# BQ76952_monitor.net
KiCad netlist of a schematic drawn in Altium Designer
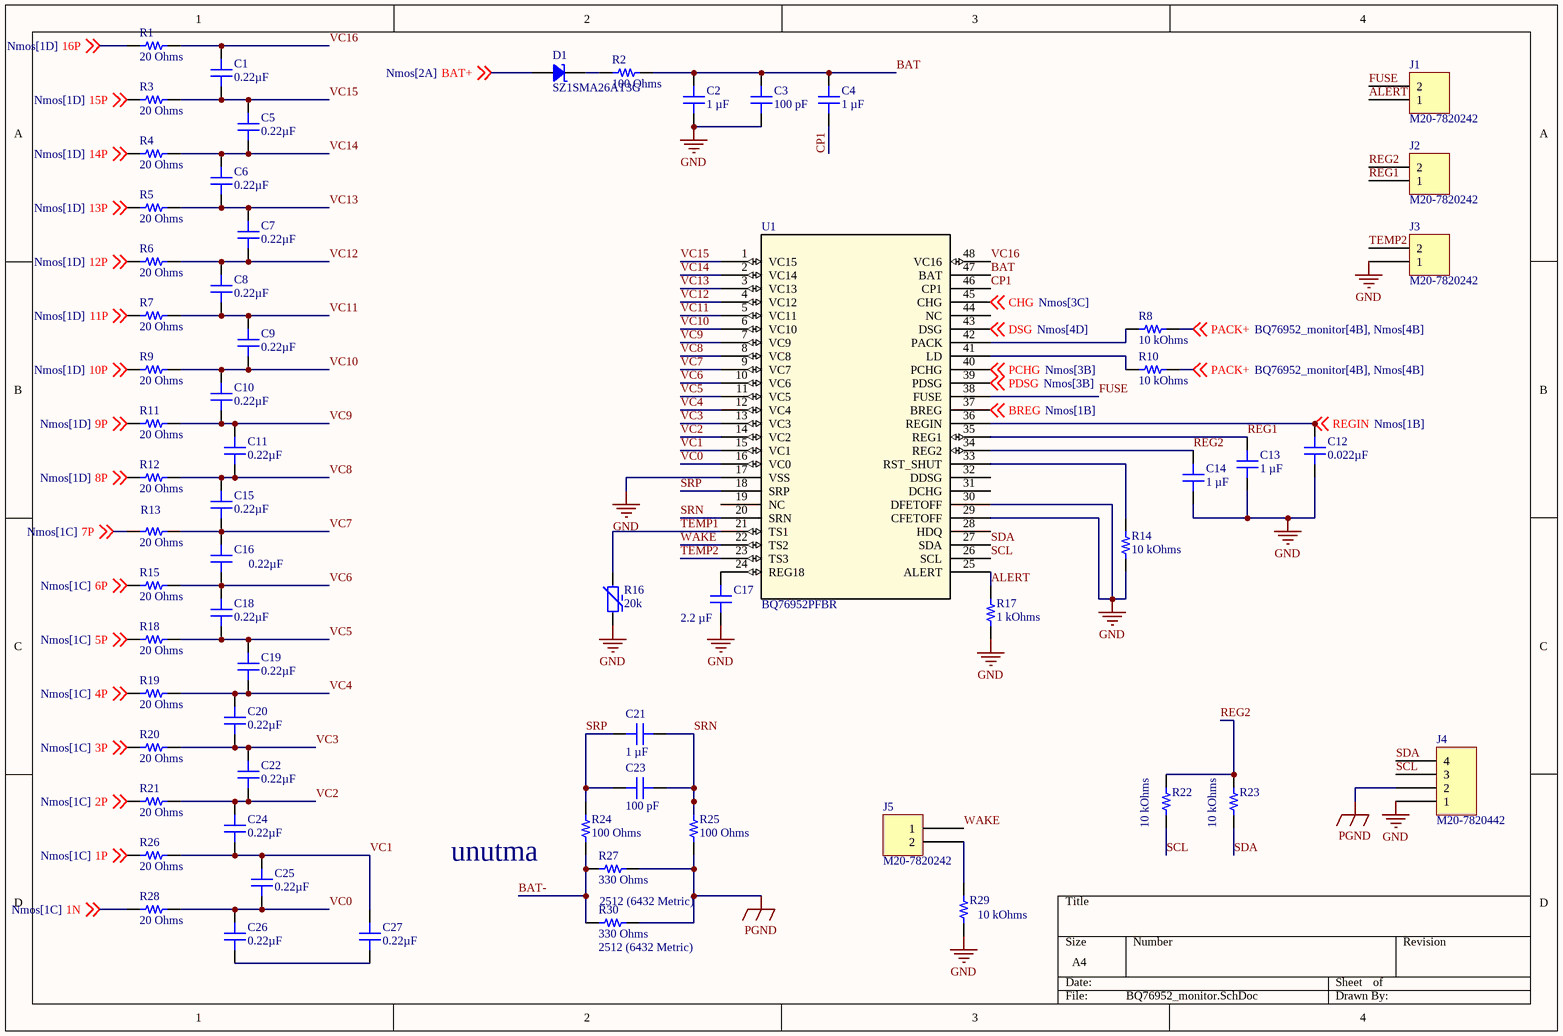
[diagram p0: BQ76952_monitor.SchDoc]

(export (version "E")
  (design (tool "Eeschema 10.0.6"))
  (components
    (comp (ref "C1")
      (value "0.22µF")
      (footprint "CAP 0805_2012")
      (description "CAP CER 0.22UF 16V X7R 0805")
      (fields
        (field (name "PART NUMBER") "0805YC224KAT2A")
        (field (name "CAPACITANCE") "0.22µF")
        (field (name "MANUFACTURER") "AVX Corporation")
      )
      (libsource (lib "Celestial Altium Library - altium_library (1)") (part "Capacitor"))
    )
    (comp (ref "C2")
      (value "1 µF")
      (footprint "CAP 0805_2012")
      (description "CAP MLCC 1UF 10% 100V X7S 0805")
      (fields
        (field (name "PART NUMBER") "HMR212CC7105KG-T")
        (field (name "CAPACITANCE") "1 µF")
        (field (name "MANUFACTURER") "Taiyo Yuden")
      )
      (libsource (lib "Celestial Altium Library - altium_library (1)") (part "Capacitor"))
    )
    (comp (ref "C3")
      (value "100 pF")
      (footprint "CAP 0805_2012")
      (description "CAP CER 100PF 100V C0G/NP0 0805")
      (fields
        (field (name "PART NUMBER") "CL21C101JC61PNC")
        (field (name "CAPACITANCE") "100 pF")
        (field (name "MANUFACTURER") "Samsung Electro-Mechanics")
      )
      (libsource (lib "Celestial Altium Library - altium_library (1)") (part "Capacitor"))
    )
    (comp (ref "C4")
      (value "1 µF")
      (footprint "CAP 0805_2012")
      (description "CAP MLCC 1UF 10% 100V X7S 0805")
      (fields
        (field (name "PART NUMBER") "HMR212CC7105KG-T")
        (field (name "CAPACITANCE") "1 µF")
        (field (name "MANUFACTURER") "Taiyo Yuden")
      )
      (libsource (lib "Celestial Altium Library - altium_library (1)") (part "Capacitor"))
    )
    (comp (ref "C5")
      (value "0.22µF")
      (footprint "CAP 0805_2012")
      (description "CAP CER 0.22UF 16V X7R 0805")
      (fields
        (field (name "PART NUMBER") "0805YC224KAT2A")
        (field (name "CAPACITANCE") "0.22µF")
        (field (name "MANUFACTURER") "AVX Corporation")
      )
      (libsource (lib "Celestial Altium Library - altium_library (1)") (part "Capacitor"))
    )
    (comp (ref "C6")
      (value "0.22µF")
      (footprint "CAP 0805_2012")
      (description "CAP CER 0.22UF 16V X7R 0805")
      (fields
        (field (name "PART NUMBER") "0805YC224KAT2A")
        (field (name "CAPACITANCE") "0.22µF")
        (field (name "MANUFACTURER") "AVX Corporation")
      )
      (libsource (lib "Celestial Altium Library - altium_library (1)") (part "Capacitor"))
    )
    (comp (ref "C7")
      (value "0.22µF")
      (footprint "CAP 0805_2012")
      (description "CAP CER 0.22UF 16V X7R 0805")
      (fields
        (field (name "PART NUMBER") "0805YC224KAT2A")
        (field (name "CAPACITANCE") "0.22µF")
        (field (name "MANUFACTURER") "AVX Corporation")
      )
      (libsource (lib "Celestial Altium Library - altium_library (1)") (part "Capacitor"))
    )
    (comp (ref "C8")
      (value "0.22µF")
      (footprint "CAP 0805_2012")
      (description "CAP CER 0.22UF 16V X7R 0805")
      (fields
        (field (name "PART NUMBER") "0805YC224KAT2A")
        (field (name "CAPACITANCE") "0.22µF")
        (field (name "MANUFACTURER") "AVX Corporation")
      )
      (libsource (lib "Celestial Altium Library - altium_library (1)") (part "Capacitor"))
    )
    (comp (ref "C9")
      (value "0.22µF")
      (footprint "CAP 0805_2012")
      (description "CAP CER 0.22UF 16V X7R 0805")
      (fields
        (field (name "PART NUMBER") "0805YC224KAT2A")
        (field (name "CAPACITANCE") "0.22µF")
        (field (name "MANUFACTURER") "AVX Corporation")
      )
      (libsource (lib "Celestial Altium Library - altium_library (1)") (part "Capacitor"))
    )
    (comp (ref "C10")
      (value "0.22µF")
      (footprint "CAP 0805_2012")
      (description "CAP CER 0.22UF 16V X7R 0805")
      (fields
        (field (name "PART NUMBER") "0805YC224KAT2A")
        (field (name "CAPACITANCE") "0.22µF")
        (field (name "MANUFACTURER") "AVX Corporation")
      )
      (libsource (lib "Celestial Altium Library - altium_library (1)") (part "Capacitor"))
    )
    (comp (ref "C11")
      (value "0.22µF")
      (footprint "CAP 0805_2012")
      (description "CAP CER 0.22UF 16V X7R 0805")
      (fields
        (field (name "PART NUMBER") "0805YC224KAT2A")
        (field (name "CAPACITANCE") "0.22µF")
        (field (name "MANUFACTURER") "AVX Corporation")
      )
      (libsource (lib "Celestial Altium Library - altium_library (1)") (part "Capacitor"))
    )
    (comp (ref "C12")
      (value "0.022µF")
      (footprint "CAP 0805_2012")
      (description "CAP CER 0.022UF 100V X7R 0805")
      (fields
        (field (name "PART NUMBER") "08051C223K4T2A")
        (field (name "CAPACITANCE") "0.022µF")
        (field (name "MANUFACTURER") "AVX Corporation")
      )
      (libsource (lib "Celestial Altium Library - altium_library (1)") (part "Capacitor"))
    )
    (comp (ref "C13")
      (value "1 µF")
      (footprint "CAP 0805_2012")
      (description "CAP CER 1UF 16V Y5V 0805")
      (fields
        (field (name "PART NUMBER") "C0805C105M4VAC7800")
        (field (name "CAPACITANCE") "1 µF")
        (field (name "MANUFACTURER") "KEMET")
      )
      (libsource (lib "Celestial Altium Library - altium_library (1)") (part "Capacitor"))
    )
    (comp (ref "C14")
      (value "1 µF")
      (footprint "CAP 0805_2012")
      (description "CAP CER 1UF 16V Y5V 0805")
      (fields
        (field (name "PART NUMBER") "C0805C105M4VAC7800")
        (field (name "CAPACITANCE") "1 µF")
        (field (name "MANUFACTURER") "KEMET")
      )
      (libsource (lib "Celestial Altium Library - altium_library (1)") (part "Capacitor"))
    )
    (comp (ref "C15")
      (value "0.22µF")
      (footprint "CAP 0805_2012")
      (description "CAP CER 0.22UF 16V X7R 0805")
      (fields
        (field (name "PART NUMBER") "0805YC224KAT2A")
        (field (name "CAPACITANCE") "0.22µF")
        (field (name "MANUFACTURER") "AVX Corporation")
      )
      (libsource (lib "Celestial Altium Library - altium_library (1)") (part "Capacitor"))
    )
    (comp (ref "C16")
      (value "0.22µF")
      (footprint "CAP 0805_2012")
      (description "CAP CER 0.22UF 16V X7R 0805")
      (fields
        (field (name "PART NUMBER") "0805YC224KAT2A")
        (field (name "CAPACITANCE") "0.22µF")
        (field (name "MANUFACTURER") "AVX Corporation")
      )
      (libsource (lib "Celestial Altium Library - altium_library (1)") (part "Capacitor"))
    )
    (comp (ref "C17")
      (value "GRM31MR71E225KA93L")
      (footprint "MURATA CAP GRM31M 1206_3216")
      (description "CAP CER 2.2UF 25V X7R 1206")
      (fields
        (field (name "CAPACITANCE") "2.2 µF")
        (field (name "MANUFACTURER") "Murata Electronics")
        (field (name "TOLERANCE") "±10%")
      )
      (libsource (lib "Celestial Altium Library - altium_library (1)") (part "Capacitor"))
    )
    (comp (ref "C18")
      (value "0.22µF")
      (footprint "CAP 0805_2012")
      (description "CAP CER 0.22UF 16V X7R 0805")
      (fields
        (field (name "PART NUMBER") "0805YC224KAT2A")
        (field (name "CAPACITANCE") "0.22µF")
        (field (name "MANUFACTURER") "AVX Corporation")
      )
      (libsource (lib "Celestial Altium Library - altium_library (1)") (part "Capacitor"))
    )
    (comp (ref "C19")
      (value "0.22µF")
      (footprint "CAP 0805_2012")
      (description "CAP CER 0.22UF 16V X7R 0805")
      (fields
        (field (name "PART NUMBER") "0805YC224KAT2A")
        (field (name "CAPACITANCE") "0.22µF")
        (field (name "MANUFACTURER") "AVX Corporation")
      )
      (libsource (lib "Celestial Altium Library - altium_library (1)") (part "Capacitor"))
    )
    (comp (ref "C20")
      (value "0.22µF")
      (footprint "CAP 0805_2012")
      (description "CAP CER 0.22UF 16V X7R 0805")
      (fields
        (field (name "PART NUMBER") "0805YC224KAT2A")
        (field (name "CAPACITANCE") "0.22µF")
        (field (name "MANUFACTURER") "AVX Corporation")
      )
      (libsource (lib "Celestial Altium Library - altium_library (1)") (part "Capacitor"))
    )
    (comp (ref "C21")
      (value "1 µF")
      (footprint "CAP 0805_2012")
      (description "CAP MLCC 1UF 10% 100V X7S 0805")
      (fields
        (field (name "PART NUMBER") "HMR212CC7105KG-T")
        (field (name "CAPACITANCE") "1 µF")
        (field (name "MANUFACTURER") "Taiyo Yuden")
      )
      (libsource (lib "Celestial Altium Library - altium_library (1)") (part "Capacitor"))
    )
    (comp (ref "C22")
      (value "0.22µF")
      (footprint "CAP 0805_2012")
      (description "CAP CER 0.22UF 16V X7R 0805")
      (fields
        (field (name "PART NUMBER") "0805YC224KAT2A")
        (field (name "CAPACITANCE") "0.22µF")
        (field (name "MANUFACTURER") "AVX Corporation")
      )
      (libsource (lib "Celestial Altium Library - altium_library (1)") (part "Capacitor"))
    )
    (comp (ref "C23")
      (value "100 pF")
      (footprint "CAP 0805_2012")
      (description "CAP CER 100PF 100V C0G/NP0 0805")
      (fields
        (field (name "PART NUMBER") "CL21C101JC61PNC")
        (field (name "CAPACITANCE") "100 pF")
        (field (name "MANUFACTURER") "Samsung Electro-Mechanics")
      )
      (libsource (lib "Celestial Altium Library - altium_library (1)") (part "Capacitor"))
    )
    (comp (ref "C24")
      (value "0.22µF")
      (footprint "CAP 0805_2012")
      (description "CAP CER 0.22UF 16V X7R 0805")
      (fields
        (field (name "PART NUMBER") "0805YC224KAT2A")
        (field (name "CAPACITANCE") "0.22µF")
        (field (name "MANUFACTURER") "AVX Corporation")
      )
      (libsource (lib "Celestial Altium Library - altium_library (1)") (part "Capacitor"))
    )
    (comp (ref "C25")
      (value "0.22µF")
      (footprint "CAP 0805_2012")
      (description "CAP CER 0.22UF 16V X7R 0805")
      (fields
        (field (name "PART NUMBER") "0805YC224KAT2A")
        (field (name "CAPACITANCE") "0.22µF")
        (field (name "MANUFACTURER") "AVX Corporation")
      )
      (libsource (lib "Celestial Altium Library - altium_library (1)") (part "Capacitor"))
    )
    (comp (ref "C26")
      (value "0.22µF")
      (footprint "CAP 0805_2012")
      (description "CAP CER 0.22UF 16V X7R 0805")
      (fields
        (field (name "PART NUMBER") "0805YC224KAT2A")
        (field (name "CAPACITANCE") "0.22µF")
        (field (name "MANUFACTURER") "AVX Corporation")
      )
      (libsource (lib "Celestial Altium Library - altium_library (1)") (part "Capacitor"))
    )
    (comp (ref "C27")
      (value "0.22µF")
      (footprint "CAP 0805_2012")
      (description "CAP CER 0.22UF 16V X7R 0805")
      (fields
        (field (name "PART NUMBER") "0805YC224KAT2A")
        (field (name "CAPACITANCE") "0.22µF")
        (field (name "MANUFACTURER") "AVX Corporation")
      )
      (libsource (lib "Celestial Altium Library - altium_library (1)") (part "Capacitor"))
    )
    (comp (ref "D1")
      (value "SZ1SMA26AT3G")
      (footprint "DO214AC SMA")
      (description "TVS DIODE 26VWM 42.1VC SMA")
      (fields (field (name "MANUFACTURER") "Littelfuse Inc."))
      (libsource (lib "Celestial Altium Library - altium_library (1)") (part "DIODE TVS UNI"))
    )
    (comp (ref "J1")
      (value "M20-7820242")
      (footprint "HARWIN M20-7820245")
      (description "CONN RCPT 2POS 0.1 GOLD PCB")
      (fields (field (name "MANUFACTURER") "Harwin Inc."))
      (libsource (lib "Celestial Altium Library - altium_library (1)") (part "2 Pin"))
    )
    (comp (ref "J2")
      (value "M20-7820242")
      (footprint "HARWIN M20-7820245")
      (description "CONN RCPT 2POS 0.1 GOLD PCB")
      (fields (field (name "MANUFACTURER") "Harwin Inc."))
      (libsource (lib "Celestial Altium Library - altium_library (1)") (part "2 Pin"))
    )
    (comp (ref "J3")
      (value "M20-7820242")
      (footprint "HARWIN M20-7820245")
      (description "CONN RCPT 2POS 0.1 GOLD PCB")
      (fields (field (name "MANUFACTURER") "Harwin Inc."))
      (libsource (lib "Celestial Altium Library - altium_library (1)") (part "2 Pin"))
    )
    (comp (ref "J4")
      (value "M20-7820442")
      (footprint "HARWIN M20-7820445")
      (description "CONN RCPT 4POS 0.1 GOLD PCB")
      (fields (field (name "MANUFACTURER") "Harwin Inc."))
      (libsource (lib "Celestial Altium Library - altium_library (1)") (part "4 Pin"))
    )
    (comp (ref "J5")
      (value "M20-7820242")
      (footprint "HARWIN M20-7820245")
      (description "CONN RCPT 2POS 0.1 GOLD PCB")
      (fields (field (name "MANUFACTURER") "Harwin Inc."))
      (libsource (lib "") (part "2 Pin_1"))
    )
    (comp (ref "R1")
      (value "20 Ohms")
      (footprint "RES 1206_3216")
      (description "RES SMD 20 OHM 1% 1/2W 1206")
      (fields (field (name "PART NUMBER") "ESR18EZPF20R0") (field (name "MANUFACTURER") "Rohm Semiconductor"))
      (libsource (lib "Celestial Altium Library - altium_library (1)") (part "Resistor"))
    )
    (comp (ref "R2")
      (value "100 Ohms")
      (footprint "RES 1206_3216")
      (description "RES 100 OHM 0.1% 1/8W 1206")
      (fields
        (field (name "PART NUMBER") "RNCS1206BKE100R")
        (field (name "MANUFACTURER") "Stackpole Electronics Inc")
      )
      (libsource (lib "Celestial Altium Library - altium_library (1)") (part "Resistor"))
    )
    (comp (ref "R3")
      (value "20 Ohms")
      (footprint "RES 1206_3216")
      (description "RES SMD 20 OHM 1% 1/2W 1206")
      (fields (field (name "PART NUMBER") "ESR18EZPF20R0") (field (name "MANUFACTURER") "Rohm Semiconductor"))
      (libsource (lib "Celestial Altium Library - altium_library (1)") (part "Resistor"))
    )
    (comp (ref "R4")
      (value "20 Ohms")
      (footprint "RES 1206_3216")
      (description "RES SMD 20 OHM 1% 1/2W 1206")
      (fields (field (name "PART NUMBER") "ESR18EZPF20R0") (field (name "MANUFACTURER") "Rohm Semiconductor"))
      (libsource (lib "Celestial Altium Library - altium_library (1)") (part "Resistor"))
    )
    (comp (ref "R5")
      (value "20 Ohms")
      (footprint "RES 1206_3216")
      (description "RES SMD 20 OHM 1% 1/2W 1206")
      (fields (field (name "PART NUMBER") "ESR18EZPF20R0") (field (name "MANUFACTURER") "Rohm Semiconductor"))
      (libsource (lib "Celestial Altium Library - altium_library (1)") (part "Resistor"))
    )
    (comp (ref "R6")
      (value "20 Ohms")
      (footprint "RES 1206_3216")
      (description "RES SMD 20 OHM 1% 1/2W 1206")
      (fields (field (name "PART NUMBER") "ESR18EZPF20R0") (field (name "MANUFACTURER") "Rohm Semiconductor"))
      (libsource (lib "Celestial Altium Library - altium_library (1)") (part "Resistor"))
    )
    (comp (ref "R7")
      (value "20 Ohms")
      (footprint "RES 1206_3216")
      (description "RES SMD 20 OHM 1% 1/2W 1206")
      (fields (field (name "PART NUMBER") "ESR18EZPF20R0") (field (name "MANUFACTURER") "Rohm Semiconductor"))
      (libsource (lib "Celestial Altium Library - altium_library (1)") (part "Resistor"))
    )
    (comp (ref "R8")
      (value "10 kOhms")
      (footprint "RES 1206_3216")
      (description "RES SMD 10K OHM 0.1% 1/4W 1206")
      (fields
        (field (name "PART NUMBER") "ERA-8ARB103V")
        (field (name "MANUFACTURER") "Panasonic Electronic Components")
      )
      (libsource (lib "Celestial Altium Library - altium_library (1)") (part "Resistor"))
    )
    (comp (ref "R9")
      (value "20 Ohms")
      (footprint "RES 1206_3216")
      (description "RES SMD 20 OHM 1% 1/2W 1206")
      (fields (field (name "PART NUMBER") "ESR18EZPF20R0") (field (name "MANUFACTURER") "Rohm Semiconductor"))
      (libsource (lib "Celestial Altium Library - altium_library (1)") (part "Resistor"))
    )
    (comp (ref "R10")
      (value "10 kOhms")
      (footprint "RES 1206_3216")
      (description "RES SMD 10K OHM 0.1% 1/4W 1206")
      (fields
        (field (name "PART NUMBER") "ERA-8ARB103V")
        (field (name "MANUFACTURER") "Panasonic Electronic Components")
      )
      (libsource (lib "Celestial Altium Library - altium_library (1)") (part "Resistor"))
    )
    (comp (ref "R11")
      (value "20 Ohms")
      (footprint "RES 1206_3216")
      (description "RES SMD 20 OHM 1% 1/2W 1206")
      (fields (field (name "PART NUMBER") "ESR18EZPF20R0") (field (name "MANUFACTURER") "Rohm Semiconductor"))
      (libsource (lib "Celestial Altium Library - altium_library (1)") (part "Resistor"))
    )
    (comp (ref "R12")
      (value "20 Ohms")
      (footprint "RES 1206_3216")
      (description "RES SMD 20 OHM 1% 1/2W 1206")
      (fields (field (name "PART NUMBER") "ESR18EZPF20R0") (field (name "MANUFACTURER") "Rohm Semiconductor"))
      (libsource (lib "Celestial Altium Library - altium_library (1)") (part "Resistor"))
    )
    (comp (ref "R13")
      (value "20 Ohms")
      (footprint "RES 1206_3216")
      (description "RES SMD 20 OHM 1% 1/2W 1206")
      (fields (field (name "PART NUMBER") "ESR18EZPF20R0") (field (name "MANUFACTURER") "Rohm Semiconductor"))
      (libsource (lib "Celestial Altium Library - altium_library (1)") (part "Resistor"))
    )
    (comp (ref "R14")
      (value "10 kOhms")
      (footprint "RES 1206_3216")
      (description "RES SMD 10K OHM 0.1% 1/4W 1206")
      (fields
        (field (name "PART NUMBER") "ERA-8ARB103V")
        (field (name "MANUFACTURER") "Panasonic Electronic Components")
      )
      (libsource (lib "Celestial Altium Library - altium_library (1)") (part "Resistor"))
    )
    (comp (ref "R15")
      (value "20 Ohms")
      (footprint "RES 1206_3216")
      (description "RES SMD 20 OHM 1% 1/2W 1206")
      (fields (field (name "PART NUMBER") "ESR18EZPF20R0") (field (name "MANUFACTURER") "Rohm Semiconductor"))
      (libsource (lib "Celestial Altium Library - altium_library (1)") (part "Resistor"))
    )
    (comp (ref "R16")
      (value "20k")
      (footprint "NTC 0805_2012")
      (description "THERMISTOR NTC 20KOHM 4000K 0805")
      (fields
        (field (name "PART NUMBER") "NHQM203B400T5")
        (field (name "MANUFACTURER") "Amphenol Advanced Sensors")
      )
      (libsource (lib "Celestial Altium Library - altium_library (1)") (part "Thermistor"))
    )
    (comp (ref "R17")
      (value "1 kOhms")
      (footprint "RES 1206_3216")
      (description "RES SMD 1K OHM 5% 1/4W 1206")
      (fields
        (field (name "PART NUMBER") "ERJ-8GEYJ102V")
        (field (name "MANUFACTURER") "Panasonic Electronic Components")
      )
      (libsource (lib "Celestial Altium Library - altium_library (1)") (part "Resistor"))
    )
    (comp (ref "R18")
      (value "20 Ohms")
      (footprint "RES 1206_3216")
      (description "RES SMD 20 OHM 1% 1/2W 1206")
      (fields (field (name "PART NUMBER") "ESR18EZPF20R0") (field (name "MANUFACTURER") "Rohm Semiconductor"))
      (libsource (lib "Celestial Altium Library - altium_library (1)") (part "Resistor"))
    )
    (comp (ref "R19")
      (value "20 Ohms")
      (footprint "RES 1206_3216")
      (description "RES SMD 20 OHM 1% 1/2W 1206")
      (fields (field (name "PART NUMBER") "ESR18EZPF20R0") (field (name "MANUFACTURER") "Rohm Semiconductor"))
      (libsource (lib "Celestial Altium Library - altium_library (1)") (part "Resistor"))
    )
    (comp (ref "R20")
      (value "20 Ohms")
      (footprint "RES 1206_3216")
      (description "RES SMD 20 OHM 1% 1/2W 1206")
      (fields (field (name "PART NUMBER") "ESR18EZPF20R0") (field (name "MANUFACTURER") "Rohm Semiconductor"))
      (libsource (lib "Celestial Altium Library - altium_library (1)") (part "Resistor"))
    )
    (comp (ref "R21")
      (value "20 Ohms")
      (footprint "RES 1206_3216")
      (description "RES SMD 20 OHM 1% 1/2W 1206")
      (fields (field (name "PART NUMBER") "ESR18EZPF20R0") (field (name "MANUFACTURER") "Rohm Semiconductor"))
      (libsource (lib "Celestial Altium Library - altium_library (1)") (part "Resistor"))
    )
    (comp (ref "R22")
      (value "10 kOhms")
      (footprint "RES 1206_3216")
      (description "RES SMD 10K OHM 0.1% 1/4W 1206")
      (fields
        (field (name "PART NUMBER") "ERA-8ARB103V")
        (field (name "MANUFACTURER") "Panasonic Electronic Components")
      )
      (libsource (lib "Celestial Altium Library - altium_library (1)") (part "Resistor"))
    )
    (comp (ref "R23")
      (value "10 kOhms")
      (footprint "RES 1206_3216")
      (description "RES SMD 10K OHM 0.1% 1/4W 1206")
      (fields
        (field (name "PART NUMBER") "ERA-8ARB103V")
        (field (name "MANUFACTURER") "Panasonic Electronic Components")
      )
      (libsource (lib "Celestial Altium Library - altium_library (1)") (part "Resistor"))
    )
    (comp (ref "R24")
      (value "100 Ohms")
      (footprint "RES 1206_3216")
      (description "RES 100 OHM 0.1% 1/8W 1206")
      (fields
        (field (name "PART NUMBER") "RNCS1206BKE100R")
        (field (name "MANUFACTURER") "Stackpole Electronics Inc")
      )
      (libsource (lib "Celestial Altium Library - altium_library (1)") (part "Resistor"))
    )
    (comp (ref "R25")
      (value "100 Ohms")
      (footprint "RES 1206_3216")
      (description "RES 100 OHM 0.1% 1/8W 1206")
      (fields
        (field (name "PART NUMBER") "RNCS1206BKE100R")
        (field (name "MANUFACTURER") "Stackpole Electronics Inc")
      )
      (libsource (lib "Celestial Altium Library - altium_library (1)") (part "Resistor"))
    )
    (comp (ref "R26")
      (value "20 Ohms")
      (footprint "RES 1206_3216")
      (description "RES SMD 20 OHM 1% 1/2W 1206")
      (fields (field (name "PART NUMBER") "ESR18EZPF20R0") (field (name "MANUFACTURER") "Rohm Semiconductor"))
      (libsource (lib "Celestial Altium Library - altium_library (1)") (part "Resistor"))
    )
    (comp (ref "R27")
      (value "330 Ohms")
      (footprint "STACKPOLE CSR2512")
      (description "RES SMD 330 OHM 1% 2W 2512")
      (fields
        (field (name "PART NUMBER") "CRM2512-FX-3300ELF")
        (field (name "PACKAGE / CASE") "2512 (6432 Metric)")
        (field (name "MANUFACTURER") "Bourns Inc.")
      )
      (libsource (lib "Celestial Altium Library - altium_library (1)") (part "Resistor"))
    )
    (comp (ref "R28")
      (value "20 Ohms")
      (footprint "RES 1206_3216")
      (description "RES SMD 20 OHM 1% 1/2W 1206")
      (fields (field (name "PART NUMBER") "ESR18EZPF20R0") (field (name "MANUFACTURER") "Rohm Semiconductor"))
      (libsource (lib "Celestial Altium Library - altium_library (1)") (part "Resistor"))
    )
    (comp (ref "R29")
      (value "10 kOhms")
      (footprint "RES 1206_3216")
      (description "RES SMD 10K OHM 0.1% 1/4W 1206")
      (fields
        (field (name "PART NUMBER") "ERA-8ARB103V")
        (field (name "MANUFACTURER") "Panasonic Electronic Components")
      )
      (libsource (lib "Celestial Altium Library - altium_library (1)") (part "Resistor"))
    )
    (comp (ref "R30")
      (value "330 Ohms")
      (footprint "STACKPOLE CSR2512")
      (description "RES SMD 330 OHM 1% 2W 2512")
      (fields
        (field (name "PART NUMBER") "CRM2512-FX-3300ELF")
        (field (name "PACKAGE / CASE") "2512 (6432 Metric)")
        (field (name "MANUFACTURER") "Bourns Inc.")
      )
      (libsource (lib "Celestial Altium Library - altium_library (1)") (part "Resistor"))
    )
    (comp (ref "U1")
      (value "BQ76952PFBR")
      (footprint "QFP_2PFBR_TEX")
      (description "No Description Available")
      (libsource (lib "BQ76952PFBR") (part "BQ76952PFBR"))
    )
  )
  (nets
    (net (code "1") (name "/ALERT") (class "Default")
      (node (ref "J1") (pin "1") (pinfunction "1_1") (pintype "passive"))
      (node (ref "R17") (pin "2") (pinfunction "2_2") (pintype "passive"))
      (node (ref "U1") (pin "25") (pinfunction "ALERT_25") (pintype "passive"))
    )
    (net (code "2") (name "/BAT") (class "Default")
      (node (ref "C2") (pin "2") (pinfunction "2_2") (pintype "passive"))
      (node (ref "C3") (pin "2") (pinfunction "2_2") (pintype "passive"))
      (node (ref "C4") (pin "2") (pinfunction "2_2") (pintype "passive"))
      (node (ref "R2") (pin "2") (pinfunction "2_2") (pintype "passive"))
      (node (ref "U1") (pin "47") (pinfunction "BAT_47") (pintype "passive"))
    )
    (net (code "3") (name "/BAT-") (class "Default")
      (node (ref "R24") (pin "1") (pinfunction "1_1") (pintype "passive"))
      (node (ref "R27") (pin "2") (pinfunction "2_2") (pintype "passive"))
      (node (ref "R30") (pin "2") (pinfunction "2_2") (pintype "passive"))
    )
    (net (code "4") (name "/CP1") (class "Default")
      (node (ref "C4") (pin "1") (pinfunction "1_1") (pintype "passive"))
      (node (ref "U1") (pin "46") (pinfunction "CP1_46") (pintype "passive"))
    )
    (net (code "5") (name "/FUSE") (class "Default")
      (node (ref "J1") (pin "2") (pinfunction "2_2") (pintype "passive"))
      (node (ref "U1") (pin "38") (pinfunction "FUSE_38") (pintype "passive"))
    )
    (net (code "6") (name "/REG1") (class "Default")
      (node (ref "C13") (pin "2") (pinfunction "2_2") (pintype "passive"))
      (node (ref "J2") (pin "1") (pinfunction "1_1") (pintype "passive"))
      (node (ref "U1") (pin "35") (pinfunction "REG1_35") (pintype "bidirectional"))
    )
    (net (code "7") (name "/REG2") (class "Default")
      (node (ref "C14") (pin "2") (pinfunction "2_2") (pintype "passive"))
      (node (ref "J2") (pin "2") (pinfunction "2_2") (pintype "passive"))
      (node (ref "R22") (pin "2") (pinfunction "2_2") (pintype "passive"))
      (node (ref "R23") (pin "2") (pinfunction "2_2") (pintype "passive"))
      (node (ref "U1") (pin "34") (pinfunction "REG2_34") (pintype "bidirectional"))
    )
    (net (code "8") (name "/SCL") (class "Default")
      (node (ref "J4") (pin "3") (pinfunction "3_3") (pintype "passive"))
      (node (ref "R22") (pin "1") (pinfunction "1_1") (pintype "passive"))
      (node (ref "U1") (pin "26") (pinfunction "SCL_26") (pintype "passive"))
    )
    (net (code "9") (name "/SDA") (class "Default")
      (node (ref "J4") (pin "4") (pinfunction "4_4") (pintype "passive"))
      (node (ref "R23") (pin "1") (pinfunction "1_1") (pintype "passive"))
      (node (ref "U1") (pin "27") (pinfunction "SDA_27") (pintype "passive"))
    )
    (net (code "10") (name "/SRN") (class "Default")
      (node (ref "C21") (pin "1") (pinfunction "1_1") (pintype "passive"))
      (node (ref "C23") (pin "1") (pinfunction "1_1") (pintype "passive"))
      (node (ref "R25") (pin "2") (pinfunction "2_2") (pintype "passive"))
      (node (ref "U1") (pin "20") (pinfunction "SRN_20") (pintype "passive"))
    )
    (net (code "11") (name "/SRP") (class "Default")
      (node (ref "C21") (pin "2") (pinfunction "2_2") (pintype "passive"))
      (node (ref "C23") (pin "2") (pinfunction "2_2") (pintype "passive"))
      (node (ref "R24") (pin "2") (pinfunction "2_2") (pintype "passive"))
      (node (ref "U1") (pin "18") (pinfunction "SRP_18") (pintype "passive"))
    )
    (net (code "12") (name "/TEMP1") (class "Default")
      (node (ref "R16") (pin "2") (pinfunction "2_2") (pintype "passive"))
      (node (ref "U1") (pin "21") (pinfunction "TS1_21") (pintype "bidirectional"))
    )
    (net (code "13") (name "/TEMP2") (class "Default")
      (node (ref "J3") (pin "2") (pinfunction "2_2") (pintype "passive"))
      (node (ref "U1") (pin "23") (pinfunction "TS3_23") (pintype "bidirectional"))
    )
    (net (code "14") (name "/VC0") (class "Default")
      (node (ref "C25") (pin "1") (pinfunction "1_1") (pintype "passive"))
      (node (ref "C26") (pin "2") (pinfunction "2_2") (pintype "passive"))
      (node (ref "R28") (pin "2") (pinfunction "2_2") (pintype "passive"))
      (node (ref "U1") (pin "16") (pinfunction "VC0_16") (pintype "bidirectional"))
    )
    (net (code "15") (name "/VC1") (class "Default")
      (node (ref "C24") (pin "1") (pinfunction "1_1") (pintype "passive"))
      (node (ref "C25") (pin "2") (pinfunction "2_2") (pintype "passive"))
      (node (ref "C27") (pin "2") (pinfunction "2_2") (pintype "passive"))
      (node (ref "R26") (pin "2") (pinfunction "2_2") (pintype "passive"))
      (node (ref "U1") (pin "15") (pinfunction "VC1_15") (pintype "bidirectional"))
    )
    (net (code "16") (name "/VC2") (class "Default")
      (node (ref "C22") (pin "1") (pinfunction "1_1") (pintype "passive"))
      (node (ref "C24") (pin "2") (pinfunction "2_2") (pintype "passive"))
      (node (ref "R21") (pin "2") (pinfunction "2_2") (pintype "passive"))
      (node (ref "U1") (pin "14") (pinfunction "VC2_14") (pintype "bidirectional"))
    )
    (net (code "17") (name "/VC3") (class "Default")
      (node (ref "C20") (pin "1") (pinfunction "1_1") (pintype "passive"))
      (node (ref "C22") (pin "2") (pinfunction "2_2") (pintype "passive"))
      (node (ref "R20") (pin "2") (pinfunction "2_2") (pintype "passive"))
      (node (ref "U1") (pin "13") (pinfunction "VC3_13") (pintype "bidirectional"))
    )
    (net (code "18") (name "/VC4") (class "Default")
      (node (ref "C19") (pin "1") (pinfunction "1_1") (pintype "passive"))
      (node (ref "C20") (pin "2") (pinfunction "2_2") (pintype "passive"))
      (node (ref "R19") (pin "2") (pinfunction "2_2") (pintype "passive"))
      (node (ref "U1") (pin "12") (pinfunction "VC4_12") (pintype "bidirectional"))
    )
    (net (code "19") (name "/VC5") (class "Default")
      (node (ref "C18") (pin "1") (pinfunction "1_1") (pintype "passive"))
      (node (ref "C19") (pin "2") (pinfunction "2_2") (pintype "passive"))
      (node (ref "R18") (pin "2") (pinfunction "2_2") (pintype "passive"))
      (node (ref "U1") (pin "11") (pinfunction "VC5_11") (pintype "bidirectional"))
    )
    (net (code "20") (name "/VC6") (class "Default")
      (node (ref "C16") (pin "1") (pinfunction "1_1") (pintype "passive"))
      (node (ref "C18") (pin "2") (pinfunction "2_2") (pintype "passive"))
      (node (ref "R15") (pin "2") (pinfunction "2_2") (pintype "passive"))
      (node (ref "U1") (pin "10") (pinfunction "VC6_10") (pintype "bidirectional"))
    )
    (net (code "21") (name "/VC7") (class "Default")
      (node (ref "C15") (pin "1") (pinfunction "1_1") (pintype "passive"))
      (node (ref "C16") (pin "2") (pinfunction "2_2") (pintype "passive"))
      (node (ref "R13") (pin "2") (pinfunction "2_2") (pintype "passive"))
      (node (ref "U1") (pin "9") (pinfunction "VC7_9") (pintype "bidirectional"))
    )
    (net (code "22") (name "/VC8") (class "Default")
      (node (ref "C11") (pin "1") (pinfunction "1_1") (pintype "passive"))
      (node (ref "C15") (pin "2") (pinfunction "2_2") (pintype "passive"))
      (node (ref "R12") (pin "2") (pinfunction "2_2") (pintype "passive"))
      (node (ref "U1") (pin "8") (pinfunction "VC8_8") (pintype "bidirectional"))
    )
    (net (code "23") (name "/VC9") (class "Default")
      (node (ref "C10") (pin "1") (pinfunction "1_1") (pintype "passive"))
      (node (ref "C11") (pin "2") (pinfunction "2_2") (pintype "passive"))
      (node (ref "R11") (pin "2") (pinfunction "2_2") (pintype "passive"))
      (node (ref "U1") (pin "7") (pinfunction "VC9_7") (pintype "bidirectional"))
    )
    (net (code "24") (name "/VC10") (class "Default")
      (node (ref "C10") (pin "2") (pinfunction "2_2") (pintype "passive"))
      (node (ref "C9") (pin "1") (pinfunction "1_1") (pintype "passive"))
      (node (ref "R9") (pin "2") (pinfunction "2_2") (pintype "passive"))
      (node (ref "U1") (pin "6") (pinfunction "VC10_6") (pintype "bidirectional"))
    )
    (net (code "25") (name "/VC11") (class "Default")
      (node (ref "C8") (pin "1") (pinfunction "1_1") (pintype "passive"))
      (node (ref "C9") (pin "2") (pinfunction "2_2") (pintype "passive"))
      (node (ref "R7") (pin "2") (pinfunction "2_2") (pintype "passive"))
      (node (ref "U1") (pin "5") (pinfunction "VC11_5") (pintype "bidirectional"))
    )
    (net (code "26") (name "/VC12") (class "Default")
      (node (ref "C7") (pin "1") (pinfunction "1_1") (pintype "passive"))
      (node (ref "C8") (pin "2") (pinfunction "2_2") (pintype "passive"))
      (node (ref "R6") (pin "2") (pinfunction "2_2") (pintype "passive"))
      (node (ref "U1") (pin "4") (pinfunction "VC12_4") (pintype "bidirectional"))
    )
    (net (code "27") (name "/VC13") (class "Default")
      (node (ref "C6") (pin "1") (pinfunction "1_1") (pintype "passive"))
      (node (ref "C7") (pin "2") (pinfunction "2_2") (pintype "passive"))
      (node (ref "R5") (pin "2") (pinfunction "2_2") (pintype "passive"))
      (node (ref "U1") (pin "3") (pinfunction "VC13_3") (pintype "bidirectional"))
    )
    (net (code "28") (name "/VC14") (class "Default")
      (node (ref "C5") (pin "1") (pinfunction "1_1") (pintype "passive"))
      (node (ref "C6") (pin "2") (pinfunction "2_2") (pintype "passive"))
      (node (ref "R4") (pin "2") (pinfunction "2_2") (pintype "passive"))
      (node (ref "U1") (pin "2") (pinfunction "VC14_2") (pintype "bidirectional"))
    )
    (net (code "29") (name "/VC15") (class "Default")
      (node (ref "C1") (pin "1") (pinfunction "1_1") (pintype "passive"))
      (node (ref "C5") (pin "2") (pinfunction "2_2") (pintype "passive"))
      (node (ref "R3") (pin "2") (pinfunction "2_2") (pintype "passive"))
      (node (ref "U1") (pin "1") (pinfunction "VC15_1") (pintype "bidirectional"))
    )
    (net (code "30") (name "/VC16") (class "Default")
      (node (ref "C1") (pin "2") (pinfunction "2_2") (pintype "passive"))
      (node (ref "R1") (pin "2") (pinfunction "2_2") (pintype "passive"))
      (node (ref "U1") (pin "48") (pinfunction "VC16_48") (pintype "bidirectional"))
    )
    (net (code "31") (name "/WAKE") (class "Default")
      (node (ref "J5") (pin "1") (pinfunction "1_1") (pintype "passive"))
      (node (ref "U1") (pin "22") (pinfunction "TS2_22") (pintype "bidirectional"))
    )
    (net (code "32") (name "1N") (class "Default")
      (node (ref "R28") (pin "1") (pinfunction "1_1") (pintype "passive"))
    )
    (net (code "33") (name "1P") (class "Default")
      (node (ref "R26") (pin "1") (pinfunction "1_1") (pintype "passive"))
    )
    (net (code "34") (name "2P") (class "Default")
      (node (ref "R21") (pin "1") (pinfunction "1_1") (pintype "passive"))
    )
    (net (code "35") (name "3P") (class "Default")
      (node (ref "R20") (pin "1") (pinfunction "1_1") (pintype "passive"))
    )
    (net (code "36") (name "4P") (class "Default")
      (node (ref "R19") (pin "1") (pinfunction "1_1") (pintype "passive"))
    )
    (net (code "37") (name "5P") (class "Default")
      (node (ref "R18") (pin "1") (pinfunction "1_1") (pintype "passive"))
    )
    (net (code "38") (name "6P") (class "Default")
      (node (ref "R15") (pin "1") (pinfunction "1_1") (pintype "passive"))
    )
    (net (code "39") (name "7P") (class "Default")
      (node (ref "R13") (pin "1") (pinfunction "1_1") (pintype "passive"))
    )
    (net (code "40") (name "8P") (class "Default")
      (node (ref "R12") (pin "1") (pinfunction "1_1") (pintype "passive"))
    )
    (net (code "41") (name "9P") (class "Default")
      (node (ref "R11") (pin "1") (pinfunction "1_1") (pintype "passive"))
    )
    (net (code "42") (name "10P") (class "Default")
      (node (ref "R9") (pin "1") (pinfunction "1_1") (pintype "passive"))
    )
    (net (code "43") (name "11P") (class "Default")
      (node (ref "R7") (pin "1") (pinfunction "1_1") (pintype "passive"))
    )
    (net (code "44") (name "12P") (class "Default")
      (node (ref "R6") (pin "1") (pinfunction "1_1") (pintype "passive"))
    )
    (net (code "45") (name "13P") (class "Default")
      (node (ref "R5") (pin "1") (pinfunction "1_1") (pintype "passive"))
    )
    (net (code "46") (name "14P") (class "Default")
      (node (ref "R4") (pin "1") (pinfunction "1_1") (pintype "passive"))
    )
    (net (code "47") (name "15P") (class "Default")
      (node (ref "R3") (pin "1") (pinfunction "1_1") (pintype "passive"))
    )
    (net (code "48") (name "16P") (class "Default")
      (node (ref "R1") (pin "1") (pinfunction "1_1") (pintype "passive"))
    )
    (net (code "49") (name "BAT+") (class "Default")
      (node (ref "D1") (pin "1") (pinfunction "1_1") (pintype "passive"))
    )
    (net (code "50") (name "BREG") (class "Default")
      (node (ref "U1") (pin "37") (pinfunction "BREG_37") (pintype "passive"))
    )
    (net (code "51") (name "CHG") (class "Default")
      (node (ref "U1") (pin "45") (pinfunction "CHG_45") (pintype "passive"))
    )
    (net (code "52") (name "DSG") (class "Default")
      (node (ref "U1") (pin "43") (pinfunction "DSG_43") (pintype "passive"))
    )
    (net (code "53") (name "GND") (class "Default")
      (node (ref "C12") (pin "1") (pinfunction "1_1") (pintype "passive"))
      (node (ref "C13") (pin "1") (pinfunction "1_1") (pintype "passive"))
      (node (ref "C14") (pin "1") (pinfunction "1_1") (pintype "passive"))
      (node (ref "C17") (pin "1") (pinfunction "1_1") (pintype "passive"))
      (node (ref "C2") (pin "1") (pinfunction "1_1") (pintype "passive"))
      (node (ref "C3") (pin "1") (pinfunction "1_1") (pintype "passive"))
      (node (ref "J3") (pin "1") (pinfunction "1_1") (pintype "passive"))
      (node (ref "J4") (pin "1") (pinfunction "1_1") (pintype "passive"))
      (node (ref "R14") (pin "2") (pinfunction "2_2") (pintype "passive"))
      (node (ref "R16") (pin "1") (pinfunction "1_1") (pintype "passive"))
      (node (ref "R17") (pin "1") (pinfunction "1_1") (pintype "passive"))
      (node (ref "R29") (pin "1") (pinfunction "1_1") (pintype "passive"))
      (node (ref "U1") (pin "17") (pinfunction "VSS_17") (pintype "power_in"))
      (node (ref "U1") (pin "29") (pinfunction "CFETOFF_29") (pintype "passive"))
      (node (ref "U1") (pin "30") (pinfunction "DFETOFF_30") (pintype "passive"))
    )
    (net (code "54") (name "Net-(C26-Pad1)") (class "Default")
      (node (ref "C26") (pin "1") (pinfunction "1_1") (pintype "passive"))
      (node (ref "C27") (pin "1") (pinfunction "1_1") (pintype "passive"))
    )
    (net (code "55") (name "Net-(D1-Pad2)") (class "Default")
      (node (ref "D1") (pin "2") (pinfunction "2_2") (pintype "passive"))
      (node (ref "R2") (pin "1") (pinfunction "1_1") (pintype "passive"))
    )
    (net (code "56") (name "Net-(J5-Pad2)") (class "Default")
      (node (ref "J5") (pin "2") (pinfunction "2_2") (pintype "passive"))
      (node (ref "R29") (pin "2") (pinfunction "2_2") (pintype "passive"))
    )
    (net (code "57") (name "Net-(U1-LD)") (class "Default")
      (node (ref "R10") (pin "2") (pinfunction "2_2") (pintype "passive"))
      (node (ref "U1") (pin "41") (pinfunction "LD_41") (pintype "passive"))
    )
    (net (code "58") (name "Net-(U1-PACK)") (class "Default")
      (node (ref "R8") (pin "2") (pinfunction "2_2") (pintype "passive"))
      (node (ref "U1") (pin "42") (pinfunction "PACK_42") (pintype "passive"))
    )
    (net (code "59") (name "Net-(U1-REG18)") (class "Default")
      (node (ref "C17") (pin "2") (pinfunction "2_2") (pintype "passive"))
      (node (ref "U1") (pin "24") (pinfunction "REG18_24") (pintype "bidirectional"))
    )
    (net (code "60") (name "Net-(U1-RST_SHUT)") (class "Default")
      (node (ref "R14") (pin "1") (pinfunction "1_1") (pintype "passive"))
      (node (ref "U1") (pin "33") (pinfunction "RST_SHUT_33") (pintype "passive"))
    )
    (net (code "61") (name "PACK+") (class "Default")
      (node (ref "R10") (pin "1") (pinfunction "1_1") (pintype "passive"))
      (node (ref "R8") (pin "1") (pinfunction "1_1") (pintype "passive"))
    )
    (net (code "62") (name "PCHG") (class "Default")
      (node (ref "U1") (pin "40") (pinfunction "PCHG_40") (pintype "passive"))
    )
    (net (code "63") (name "PDSG") (class "Default")
      (node (ref "U1") (pin "39") (pinfunction "PDSG_39") (pintype "passive"))
    )
    (net (code "64") (name "PGND") (class "Default")
      (node (ref "J4") (pin "2") (pinfunction "2_2") (pintype "passive"))
      (node (ref "R25") (pin "1") (pinfunction "1_1") (pintype "passive"))
      (node (ref "R27") (pin "1") (pinfunction "1_1") (pintype "passive"))
      (node (ref "R30") (pin "1") (pinfunction "1_1") (pintype "passive"))
    )
    (net (code "65") (name "REGIN") (class "Default")
      (node (ref "C12") (pin "2") (pinfunction "2_2") (pintype "passive"))
      (node (ref "U1") (pin "36") (pinfunction "REGIN_36") (pintype "passive"))
    )
    (net (code "66") (name "unconnected-(U1-DCHG-Pad31)") (class "Default")
      (node (ref "U1") (pin "31") (pinfunction "DCHG_31") (pintype "passive"))
    )
    (net (code "67") (name "unconnected-(U1-DDSG-Pad32)") (class "Default")
      (node (ref "U1") (pin "32") (pinfunction "DDSG_32") (pintype "passive"))
    )
    (net (code "68") (name "unconnected-(U1-HDQ-Pad28)") (class "Default")
      (node (ref "U1") (pin "28") (pinfunction "HDQ_28") (pintype "passive"))
    )
    (net (code "69") (name "unconnected-(U1-NC-Pad19)") (class "Default")
      (node (ref "U1") (pin "19") (pinfunction "NC_19") (pintype "passive"))
    )
    (net (code "70") (name "unconnected-(U1-NC-Pad44)") (class "Default")
      (node (ref "U1") (pin "44") (pinfunction "NC_44") (pintype "passive"))
    )
  )
)
